# DC_Step-Down_Converter.net
KiCad netlist of a schematic drawn in Altium Designer
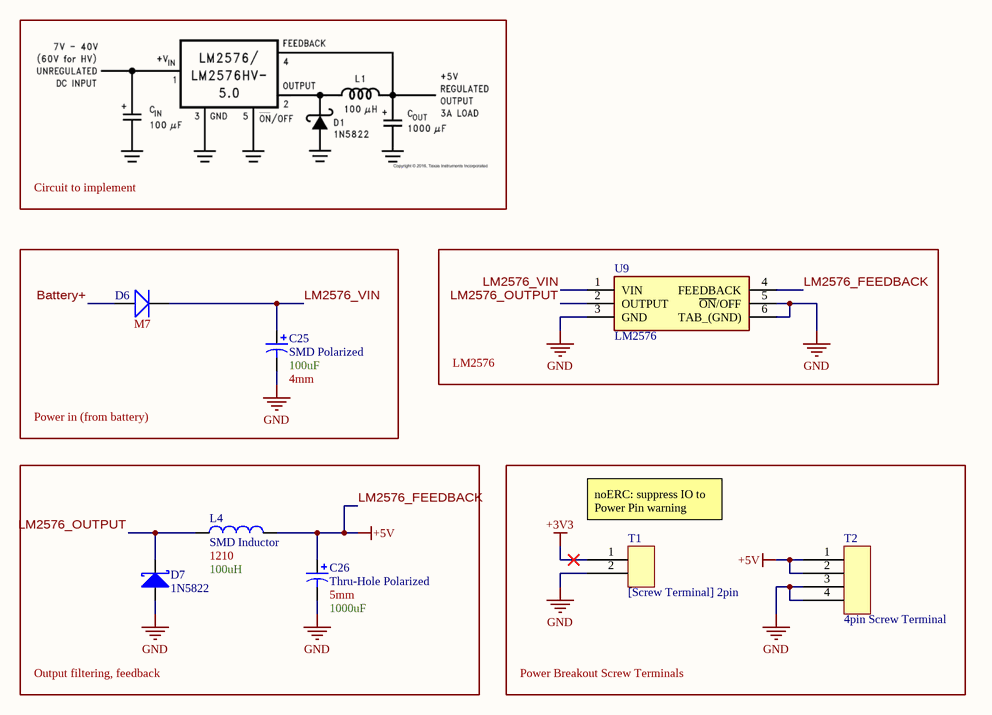
[diagram p0: DC Step-Down Converter.SchDoc]

(export (version "E")
  (design (tool "Eeschema 10.0.6"))
  (components
    (comp (ref "C25")
      (value "SMD Polarized")
      (footprint "[Cap] SMD Polarized, 4mm")
      (fields (field (name "CAPACITANCE") "100uF") (field (name "DIAMETER") "4mm"))
      (libsource (lib "RADM Components") (part "[Cap] SMD Polarized"))
    )
    (comp (ref "C26")
      (value "Thru-Hole Polarized")
      (footprint "[Cap] Thru-Hole Polarized 5mm")
      (fields (field (name "PIN SPACING") "5mm") (field (name "CAPACITANCE") "1000uF"))
      (libsource (lib "RADM Components") (part "[Cap] Thru-Hole Polarized"))
    )
    (comp (ref "D6")
      (value "Rectifier")
      (footprint "[Diode] SMD M7")
      (description "Generic")
      (fields (field (name "SIZE PACKAGE") "M7"))
      (libsource (lib "RADM Components") (part "[Diode] SMD Rectifier"))
    )
    (comp (ref "D7")
      (value "1N5822")
      (footprint "[Diode] Thru-Hole Schottky")
      (fields (field (name "MOUSER PART #") "511-1N5822"))
      (libsource (lib "RADM Components") (part "[Diode] Thru-Hole Schottky"))
    )
    (comp (ref "L4")
      (value "SMD Inductor")
      (footprint "[Inductor] SMD 1210")
      (fields (field (name "SIZE PACKAGE") "1210") (field (name "INDUCTANCE") "100uH"))
      (libsource (lib "RADM Components") (part "[Inductor] SMD Inductor"))
    )
    (comp (ref "T1")
      (value "[Screw Terminal] 2pin")
      (footprint "[Screw Terminal] 2pin")
      (libsource (lib "RADM Components") (part "[Screw Terminal] 2pin"))
    )
    (comp (ref "T2")
      (value "4pin Screw Terminal")
      (footprint "[Screw Terminal] 4pin")
      (libsource (lib "RADM Components") (part "[Screw Terminal] 4pin"))
    )
    (comp (ref "U9")
      (value "LM2576")
      (footprint "[IC] Buck Converter")
      (libsource (lib "RADM Components") (part "[IC] Buck Converter"))
    )
  )
  (nets
    (net (code "1") (name "+3V3") (class "Default") (node (ref "T1") (pin "1") (pintype "power_in")))
    (net (code "2") (name "+5V") (class "Default")
      (node (ref "C26") (pin "1") (pinfunction "1_1") (pintype "passive"))
      (node (ref "L4") (pin "2") (pinfunction "2_2") (pintype "passive"))
      (node (ref "T2") (pin "1") (pintype "power_in"))
      (node (ref "T2") (pin "2") (pintype "power_in"))
      (node (ref "U9") (pin "4") (pinfunction "FEEDBACK_4") (pintype "power_in"))
    )
    (net (code "3") (name "/Battery+") (class "Default")
      (node (ref "D6") (pin "2") (pinfunction "Anode_2") (pintype "power_in"))
    )
    (net (code "4") (name "/LM2576_OUTPUT") (class "Default")
      (node (ref "D7") (pin "1") (pinfunction "K_1") (pintype "passive"))
      (node (ref "L4") (pin "1") (pinfunction "1_1") (pintype "passive"))
      (node (ref "U9") (pin "2") (pinfunction "OUTPUT_2") (pintype "power_in"))
    )
    (net (code "5") (name "/LM2576_VIN") (class "Default")
      (node (ref "C25") (pin "1") (pinfunction "1_1") (pintype "passive"))
      (node (ref "D6") (pin "1") (pinfunction "Cathode_1") (pintype "power_in"))
      (node (ref "U9") (pin "1") (pinfunction "VIN_1") (pintype "power_in"))
    )
    (net (code "6") (name "GND") (class "Default")
      (node (ref "C25") (pin "2") (pinfunction "2_2") (pintype "passive"))
      (node (ref "C26") (pin "2") (pinfunction "2_2") (pintype "passive"))
      (node (ref "D7") (pin "2") (pinfunction "A_2") (pintype "passive"))
      (node (ref "T1") (pin "2") (pintype "power_in"))
      (node (ref "T2") (pin "3") (pintype "power_in"))
      (node (ref "T2") (pin "4") (pintype "power_in"))
      (node (ref "U9") (pin "3") (pinfunction "GND_3") (pintype "power_in"))
      (node (ref "U9") (pin "5") (pinfunction "~{ON}/OFF_5") (pintype "power_in"))
      (node (ref "U9") (pin "6") (pinfunction "TAB_(GND)_6") (pintype "power_in"))
    )
  )
)
